# photogate-sos-v2-2022.net
KiCad netlist of a schematic drawn in EAGLE
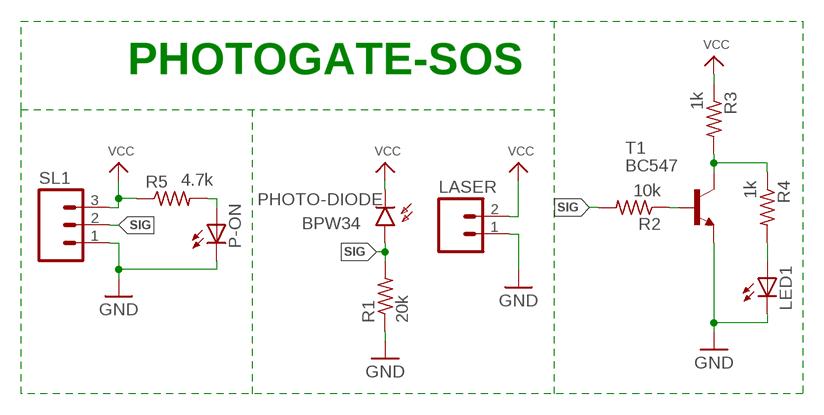
[diagram p0: schematic, sheet 1]

(export (version "E")
  (design (tool "Eeschema 10.0.6"))
  (components
    (comp (ref "LASER")
      (value "M02")
      (footprint "eagle-import:02P")
      (libsource (lib "eagle-import") (part "M02"))
    )
    (comp (ref "LED1")
      (value "LED3MM")
      (footprint "eagle-import:LED3MM")
      (libsource (lib "eagle-import") (part "LED3MM"))
    )
    (comp (ref "P-ON")
      (value "LED3MM")
      (footprint "eagle-import:LED3MM")
      (libsource (lib "eagle-import") (part "LED3MM"))
    )
    (comp (ref "PHOTO-DIODE")
      (value "BPW34")
      (footprint "eagle-import:BPW32")
      (libsource (lib "eagle-import") (part "BPW32"))
    )
    (comp (ref "R1")
      (value "20k")
      (footprint "eagle-import:0204_7")
      (libsource (lib "eagle-import") (part "R-US_0204/7"))
    )
    (comp (ref "R2")
      (value "10k")
      (footprint "eagle-import:0204_7")
      (libsource (lib "eagle-import") (part "R-US_0204/7"))
    )
    (comp (ref "R3")
      (value "1k")
      (footprint "eagle-import:0204_7")
      (libsource (lib "eagle-import") (part "R-US_0204/7"))
    )
    (comp (ref "R4")
      (value "1k")
      (footprint "eagle-import:0204_7")
      (libsource (lib "eagle-import") (part "R-US_0204/7"))
    )
    (comp (ref "R5")
      (value "4.7k")
      (footprint "eagle-import:0204_7")
      (libsource (lib "eagle-import") (part "R-US_0204/7"))
    )
    (comp (ref "SL1")
      (value "M03")
      (footprint "eagle-import:03P")
      (libsource (lib "eagle-import") (part "M03"))
    )
    (comp (ref "T1")
      (value "BC547")
      (footprint "eagle-import:TO92")
      (libsource (lib "eagle-import") (part "BC547"))
    )
  )
  (nets
    (net (code "1") (name "GND") (class "Default")
      (node (ref "LASER") (pin "1") (pinfunction "1_1") (pintype "passive"))
      (node (ref "LED1") (pin "K") (pinfunction "C_K") (pintype "passive"))
      (node (ref "P-ON") (pin "K") (pinfunction "C_K") (pintype "passive"))
      (node (ref "R1") (pin "1") (pinfunction "1_1") (pintype "passive"))
      (node (ref "SL1") (pin "1") (pinfunction "1_1") (pintype "passive"))
      (node (ref "T1") (pin "1") (pinfunction "E_1") (pintype "passive"))
    )
    (net (code "2") (name "Net-(LED1-PadA)") (class "Default")
      (node (ref "LED1") (pin "A") (pinfunction "A_A") (pintype "passive"))
      (node (ref "R4") (pin "2") (pinfunction "2_2") (pintype "passive"))
    )
    (net (code "3") (name "Net-(P-ON-PadA)") (class "Default")
      (node (ref "P-ON") (pin "A") (pinfunction "A_A") (pintype "passive"))
      (node (ref "R5") (pin "2") (pinfunction "2_2") (pintype "passive"))
    )
    (net (code "4") (name "Net-(T1-B)") (class "Default")
      (node (ref "R2") (pin "1") (pinfunction "1_1") (pintype "passive"))
      (node (ref "T1") (pin "2") (pinfunction "B_2") (pintype "passive"))
    )
    (net (code "5") (name "Net-(T1-C)") (class "Default")
      (node (ref "R3") (pin "2") (pinfunction "2_2") (pintype "passive"))
      (node (ref "R4") (pin "1") (pinfunction "1_1") (pintype "passive"))
      (node (ref "T1") (pin "3") (pinfunction "C_3") (pintype "passive"))
    )
    (net (code "6") (name "SIG") (class "Default")
      (node (ref "PHOTO-DIODE") (pin "A") (pinfunction "A_A") (pintype "passive"))
      (node (ref "R1") (pin "2") (pinfunction "2_2") (pintype "passive"))
      (node (ref "R2") (pin "2") (pinfunction "2_2") (pintype "passive"))
      (node (ref "SL1") (pin "2") (pinfunction "2_2") (pintype "passive"))
    )
    (net (code "7") (name "VCC") (class "Default")
      (node (ref "LASER") (pin "2") (pinfunction "2_2") (pintype "passive"))
      (node (ref "PHOTO-DIODE") (pin "K") (pinfunction "C_K") (pintype "passive"))
      (node (ref "R3") (pin "1") (pinfunction "1_1") (pintype "passive"))
      (node (ref "R5") (pin "1") (pinfunction "1_1") (pintype "passive"))
      (node (ref "SL1") (pin "3") (pinfunction "3_3") (pintype "passive"))
    )
  )
)
